# V4-AddOnSduino-V002.net
KiCad netlist of a schematic drawn in EAGLE
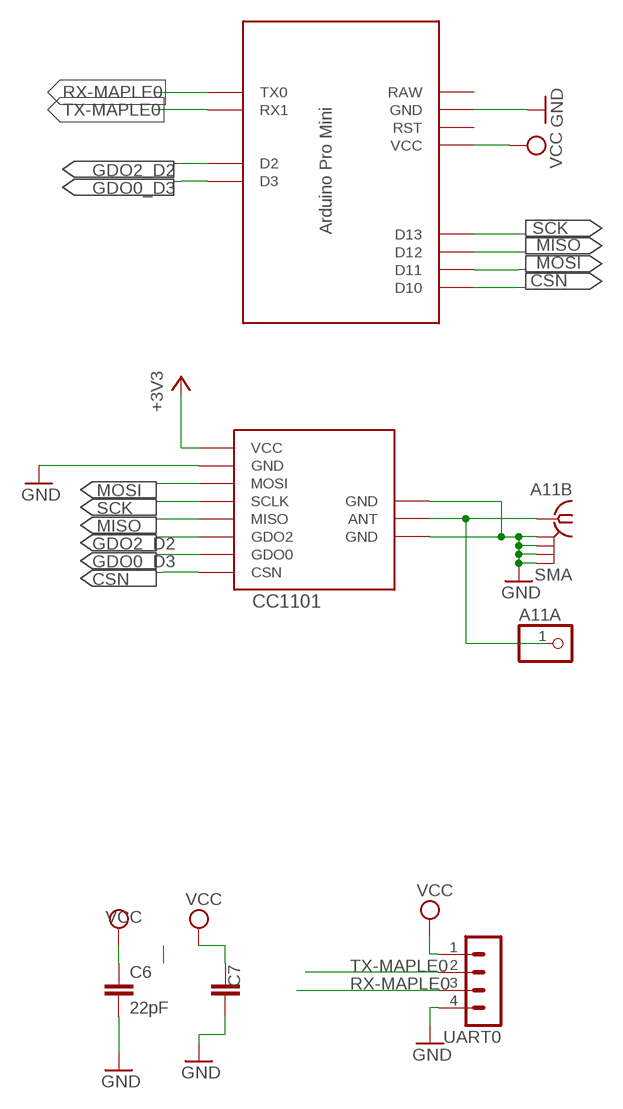
[diagram p0: schematic, sheet 1]

(export (version "E")
  (design (tool "Eeschema 10.0.6"))
  (components
    (comp (ref "A11A")
      (value "PINHD-1X1")
      (footprint "eagle-import:1X01")
      (libsource (lib "eagle-import") (part "PINHD-1X1"))
    )
    (comp (ref "A11B")
      (value "SMA")
      (footprint "eagle-import:SMA")
      (libsource (lib "eagle-import") (part "SMA"))
    )
    (comp (ref "C6")
      (value "22pF")
      (footprint "eagle-import:C0805")
      (libsource (lib "eagle-import") (part "C-EUC0805"))
    )
    (comp (ref "C7")
      (value "C-EUC1812")
      (footprint "eagle-import:C1812")
      (libsource (lib "eagle-import") (part "C-EUC1812"))
    )
    (comp (ref "CC1101")
      (value "CC1101_MODULE1SMD")
      (footprint "eagle-import:CC1101_MODULE1_SMD")
      (libsource (lib "eagle-import") (part "CC1101_MODULE1SMD"))
    )
    (comp (ref "U$2")
      (value "MARTIN-PROMINI-CC1101")
      (footprint "eagle-import:MARTIN-PRO-CC1101")
      (libsource (lib "eagle-import") (part "MARTIN-PROMINI-CC1101"))
    )
    (comp (ref "UART0")
      (value "MA04-1")
      (footprint "eagle-import:MA04-1")
      (libsource (lib "eagle-import") (part "MA04-1"))
    )
  )
  (nets
    (net (code "1") (name "+3V3") (class "Default")
      (node (ref "CC1101") (pin "VCC") (pinfunction "VCC_VCC") (pintype "power_in"))
    )
    (net (code "2") (name "/CSN") (class "Default")
      (node (ref "CC1101") (pin "CSN") (pinfunction "CSN_CSN") (pintype "bidirectional"))
      (node (ref "U$2") (pin "D10") (pinfunction "D10_D10") (pintype "bidirectional"))
    )
    (net (code "3") (name "/GDO0_D3") (class "Default")
      (node (ref "CC1101") (pin "GDO0") (pinfunction "GDO0_GDO0") (pintype "bidirectional"))
      (node (ref "U$2") (pin "D3") (pinfunction "D3_D3") (pintype "bidirectional"))
    )
    (net (code "4") (name "/GDO2_D2") (class "Default")
      (node (ref "CC1101") (pin "GDO2") (pinfunction "GDO2_GDO2") (pintype "bidirectional"))
      (node (ref "U$2") (pin "D2") (pinfunction "D2_D2") (pintype "bidirectional"))
    )
    (net (code "5") (name "/MISO") (class "Default")
      (node (ref "CC1101") (pin "MISO") (pinfunction "MISO_MISO") (pintype "bidirectional"))
      (node (ref "U$2") (pin "D12") (pinfunction "D12_D12") (pintype "bidirectional"))
    )
    (net (code "6") (name "/MOSI") (class "Default")
      (node (ref "CC1101") (pin "MOSI") (pinfunction "MOSI_MOSI") (pintype "bidirectional"))
      (node (ref "U$2") (pin "D11") (pinfunction "D11_D11") (pintype "bidirectional"))
    )
    (net (code "7") (name "/SCK") (class "Default")
      (node (ref "CC1101") (pin "SCLK") (pinfunction "SCLK_SCLK") (pintype "bidirectional"))
      (node (ref "U$2") (pin "D13") (pinfunction "D13_D13") (pintype "bidirectional"))
    )
    (net (code "8") (name "GND") (class "Default")
      (node (ref "A11B") (pin "GND@1") (pinfunction "2_GND@1") (pintype "passive"))
      (node (ref "A11B") (pin "GND@2") (pinfunction "3_GND@2") (pintype "passive"))
      (node (ref "A11B") (pin "GND@3") (pinfunction "4_GND@3") (pintype "passive"))
      (node (ref "A11B") (pin "GND@4") (pinfunction "5_GND@4") (pintype "passive"))
      (node (ref "C6") (pin "2") (pinfunction "2_2") (pintype "passive"))
      (node (ref "C7") (pin "1") (pinfunction "1_1") (pintype "passive"))
      (node (ref "CC1101") (pin "GND@0") (pinfunction "GND_GND@0") (pintype "power_in"))
      (node (ref "CC1101") (pin "GND@1") (pinfunction "GND_GND@1") (pintype "power_in"))
      (node (ref "CC1101") (pin "GND@2") (pinfunction "GND_GND@2") (pintype "power_in"))
      (node (ref "U$2") (pin "GND") (pinfunction "GND_GND") (pintype "bidirectional"))
      (node (ref "UART0") (pin "4") (pinfunction "4_4") (pintype "passive"))
    )
    (net (code "9") (name "Net-(A11A-Pad1)") (class "Default")
      (node (ref "A11A") (pin "1") (pinfunction "1_1") (pintype "passive"))
      (node (ref "A11B") (pin "1") (pinfunction "1_1") (pintype "passive"))
      (node (ref "CC1101") (pin "ANT") (pinfunction "ANT_ANT") (pintype "output"))
    )
    (net (code "10") (name "RX-MAPLE0") (class "Default")
      (node (ref "U$2") (pin "TX0") (pinfunction "TX0_TX0") (pintype "bidirectional"))
      (node (ref "UART0") (pin "3") (pinfunction "3_3") (pintype "passive"))
    )
    (net (code "11") (name "TX-MAPLE0") (class "Default")
      (node (ref "U$2") (pin "RX1") (pinfunction "RX1_RX1") (pintype "bidirectional"))
      (node (ref "UART0") (pin "2") (pinfunction "2_2") (pintype "passive"))
    )
    (net (code "12") (name "VCC") (class "Default")
      (node (ref "C6") (pin "1") (pinfunction "1_1") (pintype "passive"))
      (node (ref "C7") (pin "2") (pinfunction "2_2") (pintype "passive"))
      (node (ref "U$2") (pin "VCC") (pinfunction "VCC_VCC") (pintype "bidirectional"))
      (node (ref "UART0") (pin "1") (pinfunction "1_1") (pintype "passive"))
    )
    (net (code "13") (name "unconnected-(U$2-PadRAW)") (class "Default")
      (node (ref "U$2") (pin "RAW") (pinfunction "RAW_RAW") (pintype "bidirectional"))
    )
    (net (code "14") (name "unconnected-(U$2-PadRST)") (class "Default")
      (node (ref "U$2") (pin "RST") (pinfunction "RST_RST") (pintype "bidirectional"))
    )
  )
)
